# DAC_0.net
KiCad netlist of a schematic drawn in Altium Designer
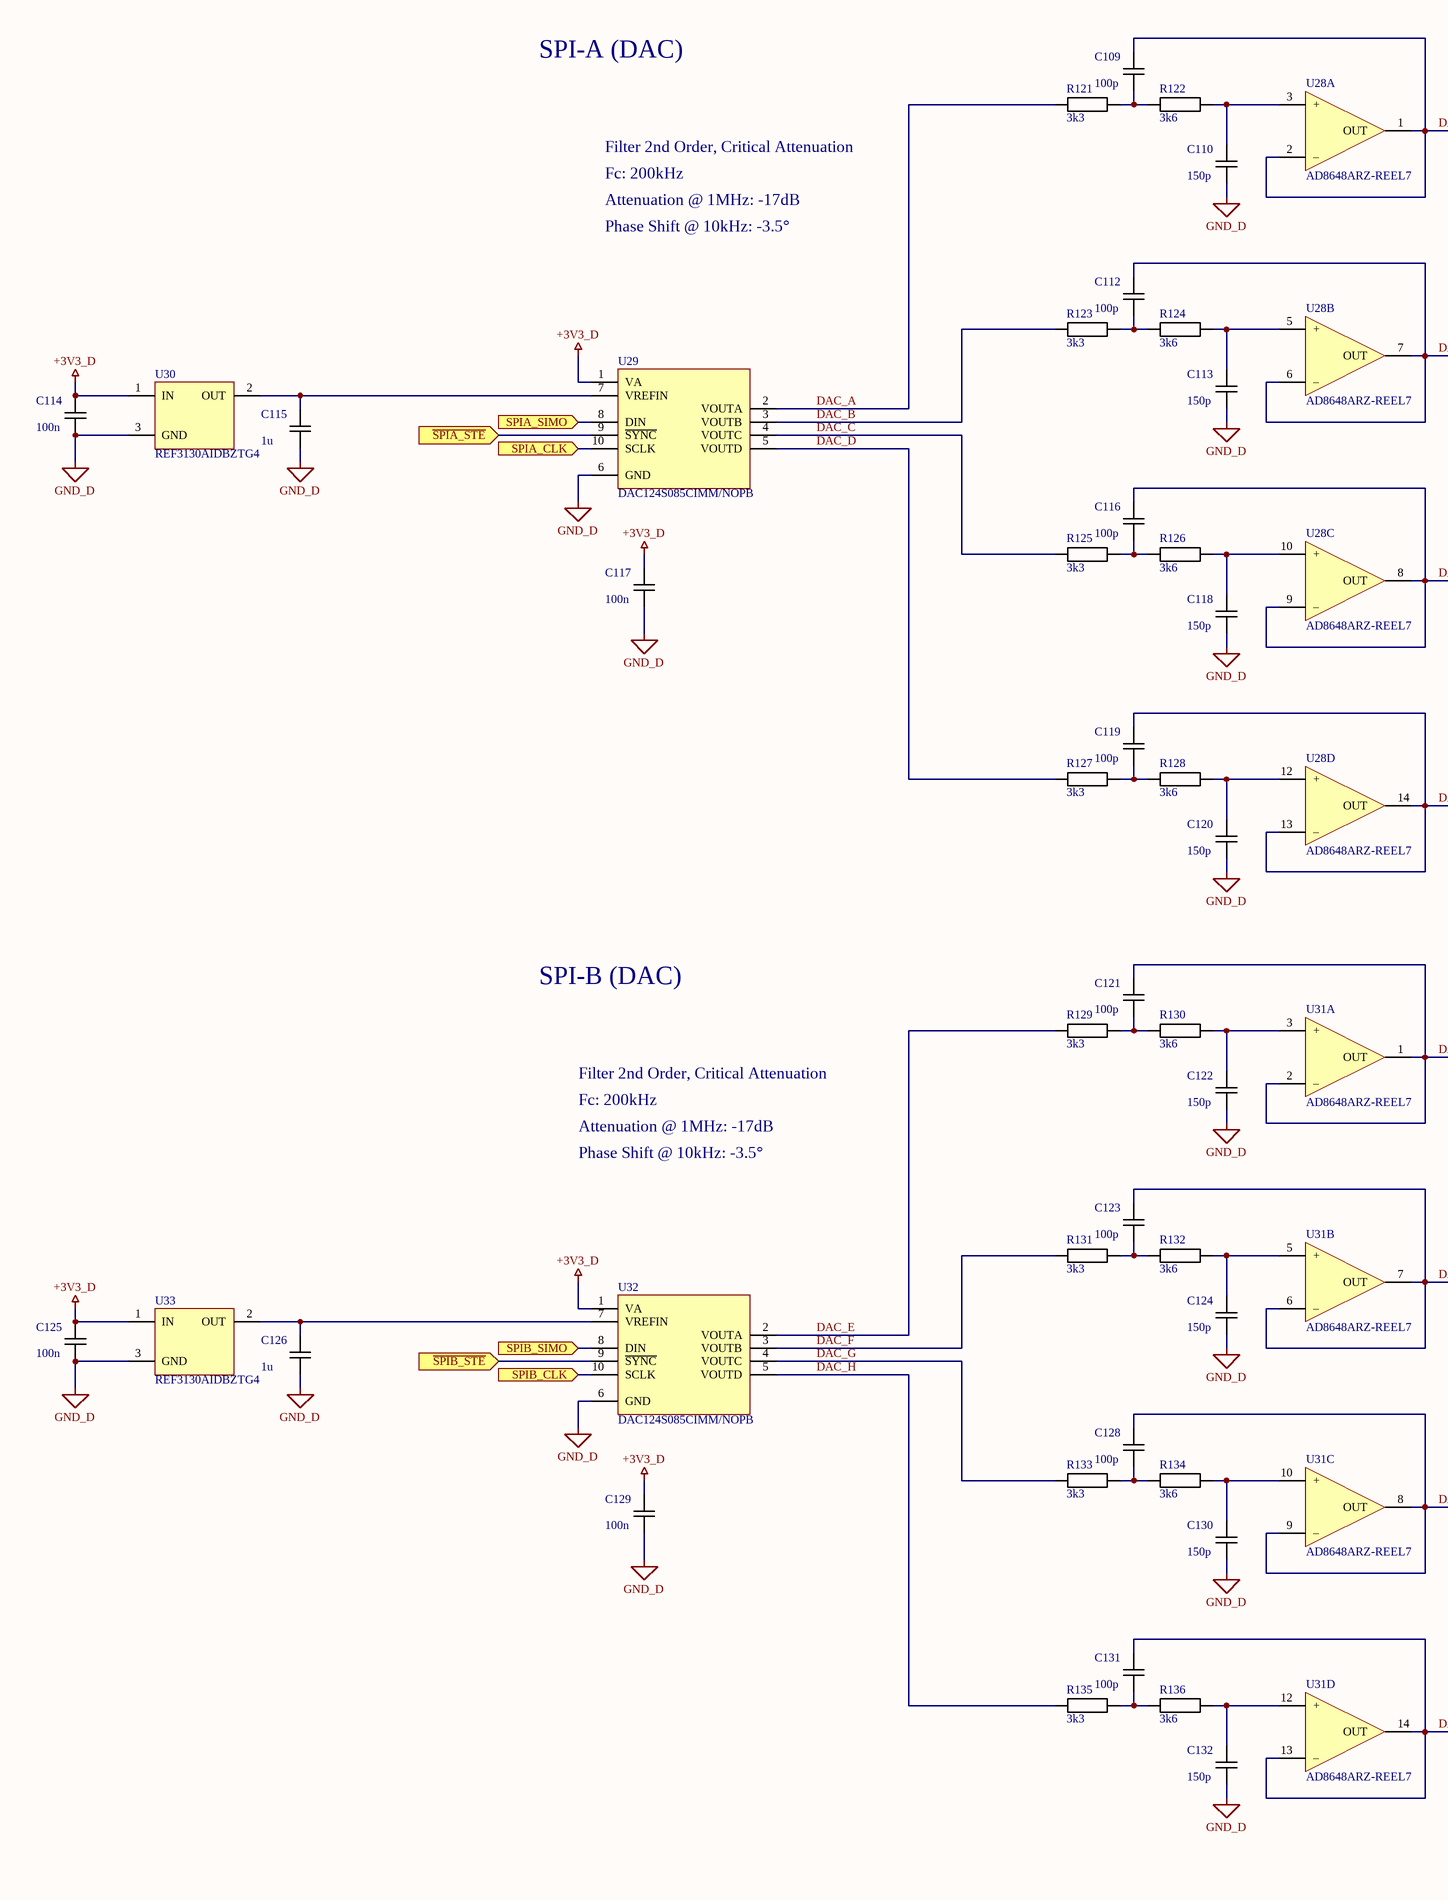
[diagram p0: DAC_0.SchDoc, left]
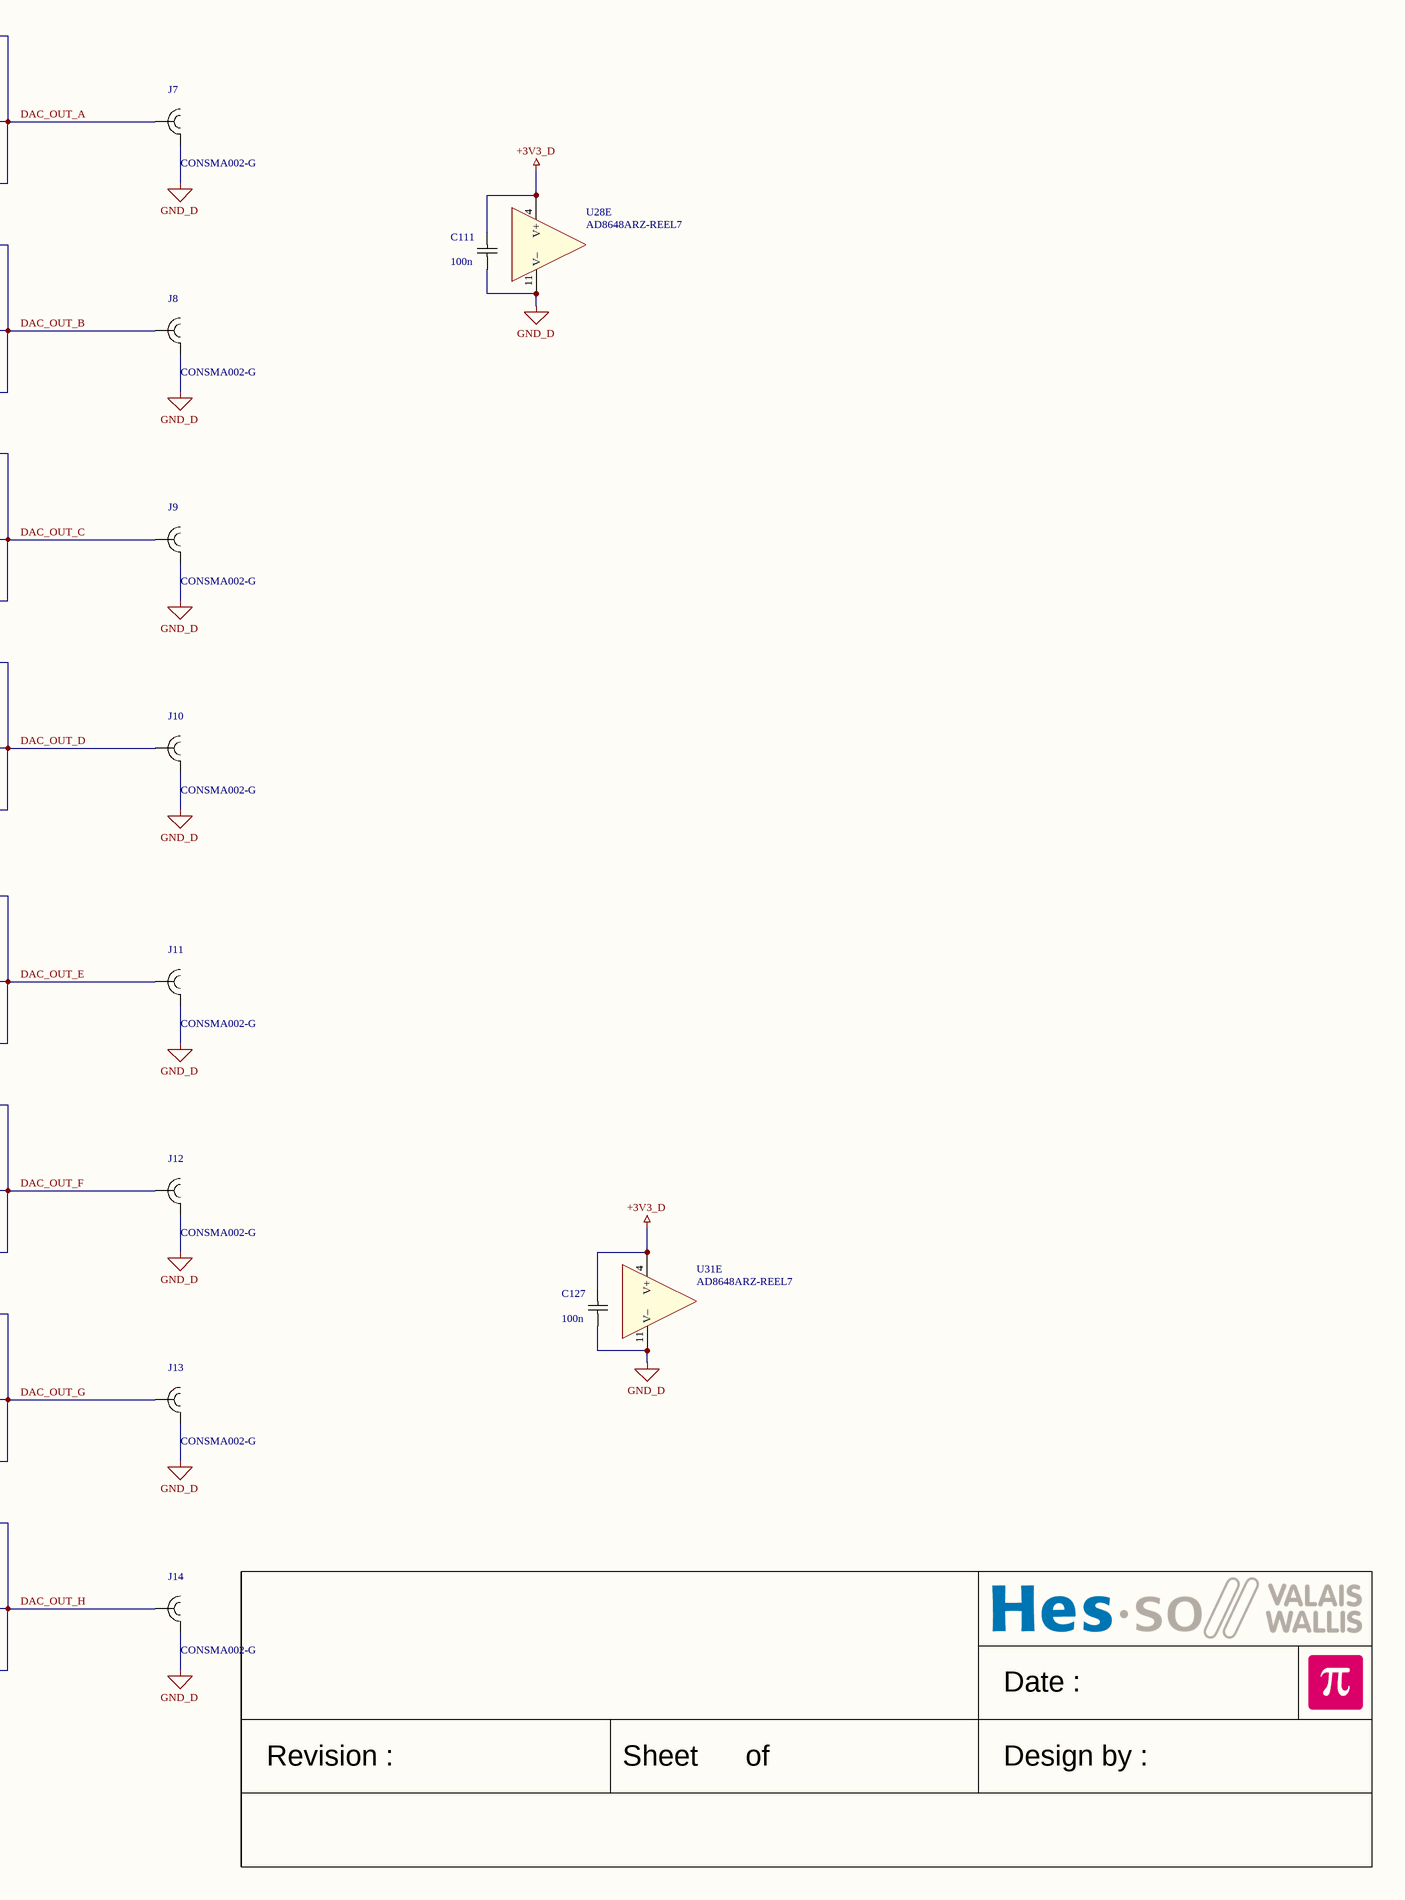
[diagram p1: DAC_0.SchDoc, right]

(export (version "E")
  (design (tool "Eeschema 10.0.6"))
  (components
    (comp (ref "C109")
      (value "100p")
      (footprint "CAPACITOR 2012 REFLOW")
      (description "Capacitor X7R 10% 50V 2012(0805)")
      (libsource (lib "Capacitor") (part "Capacitor"))
    )
    (comp (ref "C110")
      (value "150p")
      (footprint "CAPACITOR 2012 REFLOW")
      (description "Capacitor X7R 10% 50V 2012(0805)")
      (libsource (lib "Capacitor") (part "Capacitor"))
    )
    (comp (ref "C111")
      (value "100n")
      (footprint "CAPACITOR 1608 REFLOW")
      (description "Capacitor X7R 10% 50V 1608(0603)")
      (libsource (lib "Capacitor") (part "Capacitor"))
    )
    (comp (ref "C112")
      (value "100p")
      (footprint "CAPACITOR 2012 REFLOW")
      (description "Capacitor X7R 10% 50V 2012(0805)")
      (libsource (lib "Capacitor") (part "Capacitor"))
    )
    (comp (ref "C113")
      (value "150p")
      (footprint "CAPACITOR 2012 REFLOW")
      (description "Capacitor X7R 10% 50V 2012(0805)")
      (libsource (lib "Capacitor") (part "Capacitor"))
    )
    (comp (ref "C114")
      (value "100n")
      (footprint "CAPACITOR 2012 REFLOW")
      (description "Capacitor X7R 10% 50V 2012(0805)")
      (libsource (lib "Capacitor") (part "Capacitor"))
    )
    (comp (ref "C115")
      (value "1u")
      (footprint "CAPACITOR 2012 REFLOW")
      (description "Capacitor X7R 10% 10V 2012(0805)")
      (libsource (lib "Capacitor") (part "Capacitor"))
    )
    (comp (ref "C116")
      (value "100p")
      (footprint "CAPACITOR 2012 REFLOW")
      (description "Capacitor X7R 10% 50V 2012(0805)")
      (libsource (lib "Capacitor") (part "Capacitor"))
    )
    (comp (ref "C117")
      (value "100n")
      (footprint "CAPACITOR 1608 REFLOW")
      (description "Capacitor X7R 10% 50V 1608(0603)")
      (libsource (lib "Capacitor") (part "Capacitor"))
    )
    (comp (ref "C118")
      (value "150p")
      (footprint "CAPACITOR 2012 REFLOW")
      (description "Capacitor X7R 10% 50V 2012(0805)")
      (libsource (lib "Capacitor") (part "Capacitor"))
    )
    (comp (ref "C119")
      (value "100p")
      (footprint "CAPACITOR 2012 REFLOW")
      (description "Capacitor X7R 10% 50V 2012(0805)")
      (libsource (lib "Capacitor") (part "Capacitor"))
    )
    (comp (ref "C120")
      (value "150p")
      (footprint "CAPACITOR 2012 REFLOW")
      (description "Capacitor X7R 10% 50V 2012(0805)")
      (libsource (lib "Capacitor") (part "Capacitor"))
    )
    (comp (ref "C121")
      (value "100p")
      (footprint "CAPACITOR 2012 REFLOW")
      (description "Capacitor X7R 10% 50V 2012(0805)")
      (libsource (lib "Capacitor") (part "Capacitor"))
    )
    (comp (ref "C122")
      (value "150p")
      (footprint "CAPACITOR 2012 REFLOW")
      (description "Capacitor X7R 10% 50V 2012(0805)")
      (libsource (lib "Capacitor") (part "Capacitor"))
    )
    (comp (ref "C123")
      (value "100p")
      (footprint "CAPACITOR 2012 REFLOW")
      (description "Capacitor X7R 10% 50V 2012(0805)")
      (libsource (lib "Capacitor") (part "Capacitor"))
    )
    (comp (ref "C124")
      (value "150p")
      (footprint "CAPACITOR 2012 REFLOW")
      (description "Capacitor X7R 10% 50V 2012(0805)")
      (libsource (lib "Capacitor") (part "Capacitor"))
    )
    (comp (ref "C125")
      (value "100n")
      (footprint "CAPACITOR 2012 REFLOW")
      (description "Capacitor X7R 10% 50V 2012(0805)")
      (libsource (lib "Capacitor") (part "Capacitor"))
    )
    (comp (ref "C126")
      (value "1u")
      (footprint "CAPACITOR 2012 REFLOW")
      (description "Capacitor X7R 10% 10V 2012(0805)")
      (libsource (lib "Capacitor") (part "Capacitor"))
    )
    (comp (ref "C127")
      (value "100n")
      (footprint "CAPACITOR 1608 REFLOW")
      (description "Capacitor X7R 10% 50V 1608(0603)")
      (libsource (lib "Capacitor") (part "Capacitor"))
    )
    (comp (ref "C128")
      (value "100p")
      (footprint "CAPACITOR 2012 REFLOW")
      (description "Capacitor X7R 10% 50V 2012(0805)")
      (libsource (lib "Capacitor") (part "Capacitor"))
    )
    (comp (ref "C129")
      (value "100n")
      (footprint "CAPACITOR 1608 REFLOW")
      (description "Capacitor X7R 10% 50V 1608(0603)")
      (libsource (lib "Capacitor") (part "Capacitor"))
    )
    (comp (ref "C130")
      (value "150p")
      (footprint "CAPACITOR 2012 REFLOW")
      (description "Capacitor X7R 10% 50V 2012(0805)")
      (libsource (lib "Capacitor") (part "Capacitor"))
    )
    (comp (ref "C131")
      (value "100p")
      (footprint "CAPACITOR 2012 REFLOW")
      (description "Capacitor X7R 10% 50V 2012(0805)")
      (libsource (lib "Capacitor") (part "Capacitor"))
    )
    (comp (ref "C132")
      (value "150p")
      (footprint "CAPACITOR 2012 REFLOW")
      (description "Capacitor X7R 10% 50V 2012(0805)")
      (libsource (lib "Capacitor") (part "Capacitor"))
    )
    (comp (ref "J7")
      (value "CONSMA002-G")
      (footprint "SMA TH Right Angle Linx CONSMA002")
      (description "SMA TH RIGHT ANGLE LINX CONSMA002")
      (fields (field (name "MANUFACTURER") "Linx Technologies"))
      (libsource (lib "Connector") (part "SMA TH RIGHT ANGLE LINX CONSMA002"))
    )
    (comp (ref "J8")
      (value "CONSMA002-G")
      (footprint "SMA TH Right Angle Linx CONSMA002")
      (description "SMA TH RIGHT ANGLE LINX CONSMA002")
      (fields (field (name "MANUFACTURER") "Linx Technologies"))
      (libsource (lib "Connector") (part "SMA TH RIGHT ANGLE LINX CONSMA002"))
    )
    (comp (ref "J9")
      (value "CONSMA002-G")
      (footprint "SMA TH Right Angle Linx CONSMA002")
      (description "SMA TH RIGHT ANGLE LINX CONSMA002")
      (fields (field (name "MANUFACTURER") "Linx Technologies"))
      (libsource (lib "Connector") (part "SMA TH RIGHT ANGLE LINX CONSMA002"))
    )
    (comp (ref "J10")
      (value "CONSMA002-G")
      (footprint "SMA TH Right Angle Linx CONSMA002")
      (description "SMA TH RIGHT ANGLE LINX CONSMA002")
      (fields (field (name "MANUFACTURER") "Linx Technologies"))
      (libsource (lib "Connector") (part "SMA TH RIGHT ANGLE LINX CONSMA002"))
    )
    (comp (ref "J11")
      (value "CONSMA002-G")
      (footprint "SMA TH Right Angle Linx CONSMA002")
      (description "SMA TH RIGHT ANGLE LINX CONSMA002")
      (fields (field (name "MANUFACTURER") "Linx Technologies"))
      (libsource (lib "Connector") (part "SMA TH RIGHT ANGLE LINX CONSMA002"))
    )
    (comp (ref "J12")
      (value "CONSMA002-G")
      (footprint "SMA TH Right Angle Linx CONSMA002")
      (description "SMA TH RIGHT ANGLE LINX CONSMA002")
      (fields (field (name "MANUFACTURER") "Linx Technologies"))
      (libsource (lib "Connector") (part "SMA TH RIGHT ANGLE LINX CONSMA002"))
    )
    (comp (ref "J13")
      (value "CONSMA002-G")
      (footprint "SMA TH Right Angle Linx CONSMA002")
      (description "SMA TH RIGHT ANGLE LINX CONSMA002")
      (fields (field (name "MANUFACTURER") "Linx Technologies"))
      (libsource (lib "Connector") (part "SMA TH RIGHT ANGLE LINX CONSMA002"))
    )
    (comp (ref "J14")
      (value "CONSMA002-G")
      (footprint "SMA TH Right Angle Linx CONSMA002")
      (description "SMA TH RIGHT ANGLE LINX CONSMA002")
      (fields (field (name "MANUFACTURER") "Linx Technologies"))
      (libsource (lib "Connector") (part "SMA TH RIGHT ANGLE LINX CONSMA002"))
    )
    (comp (ref "R121")
      (value "3k3")
      (footprint "RESISTOR 2012 REFLOW")
      (description "Resistor 1% 50V 125mW 2012(0805)")
      (libsource (lib "Resistor") (part "Resistor"))
    )
    (comp (ref "R122")
      (value "3k6")
      (footprint "RESISTOR 2012 REFLOW")
      (description "Resistor 1% 50V 125mW 2012(0805)")
      (libsource (lib "Resistor") (part "Resistor"))
    )
    (comp (ref "R123")
      (value "3k3")
      (footprint "RESISTOR 2012 REFLOW")
      (description "Resistor 1% 50V 125mW 2012(0805)")
      (libsource (lib "Resistor") (part "Resistor"))
    )
    (comp (ref "R124")
      (value "3k6")
      (footprint "RESISTOR 2012 REFLOW")
      (description "Resistor 1% 50V 125mW 2012(0805)")
      (libsource (lib "Resistor") (part "Resistor"))
    )
    (comp (ref "R125")
      (value "3k3")
      (footprint "RESISTOR 2012 REFLOW")
      (description "Resistor 1% 50V 125mW 2012(0805)")
      (libsource (lib "Resistor") (part "Resistor"))
    )
    (comp (ref "R126")
      (value "3k6")
      (footprint "RESISTOR 2012 REFLOW")
      (description "Resistor 1% 50V 125mW 2012(0805)")
      (libsource (lib "Resistor") (part "Resistor"))
    )
    (comp (ref "R127")
      (value "3k3")
      (footprint "RESISTOR 2012 REFLOW")
      (description "Resistor 1% 50V 125mW 2012(0805)")
      (libsource (lib "Resistor") (part "Resistor"))
    )
    (comp (ref "R128")
      (value "3k6")
      (footprint "RESISTOR 2012 REFLOW")
      (description "Resistor 1% 50V 125mW 2012(0805)")
      (libsource (lib "Resistor") (part "Resistor"))
    )
    (comp (ref "R129")
      (value "3k3")
      (footprint "RESISTOR 2012 REFLOW")
      (description "Resistor 1% 50V 125mW 2012(0805)")
      (libsource (lib "Resistor") (part "Resistor"))
    )
    (comp (ref "R130")
      (value "3k6")
      (footprint "RESISTOR 2012 REFLOW")
      (description "Resistor 1% 50V 125mW 2012(0805)")
      (libsource (lib "Resistor") (part "Resistor"))
    )
    (comp (ref "R131")
      (value "3k3")
      (footprint "RESISTOR 2012 REFLOW")
      (description "Resistor 1% 50V 125mW 2012(0805)")
      (libsource (lib "Resistor") (part "Resistor"))
    )
    (comp (ref "R132")
      (value "3k6")
      (footprint "RESISTOR 2012 REFLOW")
      (description "Resistor 1% 50V 125mW 2012(0805)")
      (libsource (lib "Resistor") (part "Resistor"))
    )
    (comp (ref "R133")
      (value "3k3")
      (footprint "RESISTOR 2012 REFLOW")
      (description "Resistor 1% 50V 125mW 2012(0805)")
      (libsource (lib "Resistor") (part "Resistor"))
    )
    (comp (ref "R134")
      (value "3k6")
      (footprint "RESISTOR 2012 REFLOW")
      (description "Resistor 1% 50V 125mW 2012(0805)")
      (libsource (lib "Resistor") (part "Resistor"))
    )
    (comp (ref "R135")
      (value "3k3")
      (footprint "RESISTOR 2012 REFLOW")
      (description "Resistor 1% 50V 125mW 2012(0805)")
      (libsource (lib "Resistor") (part "Resistor"))
    )
    (comp (ref "R136")
      (value "3k6")
      (footprint "RESISTOR 2012 REFLOW")
      (description "Resistor 1% 50V 125mW 2012(0805)")
      (libsource (lib "Resistor") (part "Resistor"))
    )
    (comp (ref "U28")
      (value "AD8648ARZ-REEL7")
      (footprint "SO14 P1.27 C4.0X8.8 H1.75")
      (description "Generic quad OPA 14 pins")
      (fields (field (name "MANUFACTURER") "Analog Devices"))
      (libsource (lib "Amplifier") (part "OPA QUAD"))
    )
    (comp (ref "U29")
      (value "DAC124S085CIMM/NOPB")
      (footprint "VSSOP10 P0.5 C3.1X3.1 H1.1")
      (description "DAC124S085 12-Bit Micro Power Quad Digital-to-Analog Converter With Rail-to-Rail Output")
      (fields (field (name "MANUFACTURER") "Texas Instruments"))
      (libsource (lib "Converter") (part "DAC124S085CIMM"))
    )
    (comp (ref "U30")
      (value "REF3130AIDBZTG4")
      (footprint "SOT23 P0.95 C1.6x3.0 H1.3")
      (description "Generic Positive Voltage Reference")
      (libsource (lib "Regulator") (part "REFERENCE SOT23 IN,OUT,GND"))
    )
    (comp (ref "U31")
      (value "AD8648ARZ-REEL7")
      (footprint "SO14 P1.27 C4.0X8.8 H1.75")
      (description "Generic quad OPA 14 pins")
      (fields (field (name "MANUFACTURER") "Analog Devices"))
      (libsource (lib "Amplifier") (part "OPA QUAD"))
    )
    (comp (ref "U32")
      (value "DAC124S085CIMM/NOPB")
      (footprint "VSSOP10 P0.5 C3.1X3.1 H1.1")
      (description "DAC124S085 12-Bit Micro Power Quad Digital-to-Analog Converter With Rail-to-Rail Output")
      (fields (field (name "MANUFACTURER") "Texas Instruments"))
      (libsource (lib "Converter") (part "DAC124S085CIMM"))
    )
    (comp (ref "U33")
      (value "REF3130AIDBZTG4")
      (footprint "SOT23 P0.95 C1.6x3.0 H1.3")
      (description "Generic Positive Voltage Reference")
      (libsource (lib "Regulator") (part "REFERENCE SOT23 IN,OUT,GND"))
    )
  )
  (nets
    (net (code "1") (name "+3V3_D") (class "Default")
      (node (ref "C111") (pin "2") (pinfunction "2_2") (pintype "passive"))
      (node (ref "C114") (pin "2") (pinfunction "2_2") (pintype "passive"))
      (node (ref "C117") (pin "2") (pinfunction "2_2") (pintype "passive"))
      (node (ref "C125") (pin "2") (pinfunction "2_2") (pintype "passive"))
      (node (ref "C127") (pin "2") (pinfunction "2_2") (pintype "passive"))
      (node (ref "C129") (pin "2") (pinfunction "2_2") (pintype "passive"))
      (node (ref "U28") (pin "4") (pinfunction "V+_4") (pintype "passive"))
      (node (ref "U29") (pin "1") (pinfunction "VA_1") (pintype "passive"))
      (node (ref "U30") (pin "1") (pinfunction "IN_1") (pintype "passive"))
      (node (ref "U31") (pin "4") (pinfunction "V+_4") (pintype "passive"))
      (node (ref "U32") (pin "1") (pinfunction "VA_1") (pintype "passive"))
      (node (ref "U33") (pin "1") (pinfunction "IN_1") (pintype "passive"))
    )
    (net (code "2") (name "/DAC_A") (class "Default")
      (node (ref "R121") (pin "1") (pinfunction "1_1") (pintype "passive"))
      (node (ref "U29") (pin "2") (pinfunction "VOUTA_2") (pintype "passive"))
    )
    (net (code "3") (name "/DAC_B") (class "Default")
      (node (ref "R123") (pin "1") (pinfunction "1_1") (pintype "passive"))
      (node (ref "U29") (pin "3") (pinfunction "VOUTB_3") (pintype "passive"))
    )
    (net (code "4") (name "/DAC_C") (class "Default")
      (node (ref "R125") (pin "1") (pinfunction "1_1") (pintype "passive"))
      (node (ref "U29") (pin "4") (pinfunction "VOUTC_4") (pintype "passive"))
    )
    (net (code "5") (name "/DAC_D") (class "Default")
      (node (ref "R127") (pin "1") (pinfunction "1_1") (pintype "passive"))
      (node (ref "U29") (pin "5") (pinfunction "VOUTD_5") (pintype "passive"))
    )
    (net (code "6") (name "/DAC_E") (class "Default")
      (node (ref "R129") (pin "1") (pinfunction "1_1") (pintype "passive"))
      (node (ref "U32") (pin "2") (pinfunction "VOUTA_2") (pintype "passive"))
    )
    (net (code "7") (name "/DAC_F") (class "Default")
      (node (ref "R131") (pin "1") (pinfunction "1_1") (pintype "passive"))
      (node (ref "U32") (pin "3") (pinfunction "VOUTB_3") (pintype "passive"))
    )
    (net (code "8") (name "/DAC_G") (class "Default")
      (node (ref "R133") (pin "1") (pinfunction "1_1") (pintype "passive"))
      (node (ref "U32") (pin "4") (pinfunction "VOUTC_4") (pintype "passive"))
    )
    (net (code "9") (name "/DAC_H") (class "Default")
      (node (ref "R135") (pin "1") (pinfunction "1_1") (pintype "passive"))
      (node (ref "U32") (pin "5") (pinfunction "VOUTD_5") (pintype "passive"))
    )
    (net (code "10") (name "/DAC_OUT_A") (class "Default")
      (node (ref "C109") (pin "2") (pinfunction "2_2") (pintype "passive"))
      (node (ref "J7") (pin "1") (pinfunction "1_1") (pintype "passive"))
      (node (ref "U28") (pin "1") (pinfunction "OUT_1") (pintype "passive"))
      (node (ref "U28") (pin "2") (pinfunction "–_2") (pintype "passive"))
    )
    (net (code "11") (name "/DAC_OUT_B") (class "Default")
      (node (ref "C112") (pin "2") (pinfunction "2_2") (pintype "passive"))
      (node (ref "J8") (pin "1") (pinfunction "1_1") (pintype "passive"))
      (node (ref "U28") (pin "6") (pinfunction "–_6") (pintype "passive"))
      (node (ref "U28") (pin "7") (pinfunction "OUT_7") (pintype "passive"))
    )
    (net (code "12") (name "/DAC_OUT_C") (class "Default")
      (node (ref "C116") (pin "2") (pinfunction "2_2") (pintype "passive"))
      (node (ref "J9") (pin "1") (pinfunction "1_1") (pintype "passive"))
      (node (ref "U28") (pin "8") (pinfunction "OUT_8") (pintype "passive"))
      (node (ref "U28") (pin "9") (pinfunction "–_9") (pintype "passive"))
    )
    (net (code "13") (name "/DAC_OUT_D") (class "Default")
      (node (ref "C119") (pin "2") (pinfunction "2_2") (pintype "passive"))
      (node (ref "J10") (pin "1") (pinfunction "1_1") (pintype "passive"))
      (node (ref "U28") (pin "13") (pinfunction "–_13") (pintype "passive"))
      (node (ref "U28") (pin "14") (pinfunction "OUT_14") (pintype "passive"))
    )
    (net (code "14") (name "/DAC_OUT_E") (class "Default")
      (node (ref "C121") (pin "2") (pinfunction "2_2") (pintype "passive"))
      (node (ref "J11") (pin "1") (pinfunction "1_1") (pintype "passive"))
      (node (ref "U31") (pin "1") (pinfunction "OUT_1") (pintype "passive"))
      (node (ref "U31") (pin "2") (pinfunction "–_2") (pintype "passive"))
    )
    (net (code "15") (name "/DAC_OUT_F") (class "Default")
      (node (ref "C123") (pin "2") (pinfunction "2_2") (pintype "passive"))
      (node (ref "J12") (pin "1") (pinfunction "1_1") (pintype "passive"))
      (node (ref "U31") (pin "6") (pinfunction "–_6") (pintype "passive"))
      (node (ref "U31") (pin "7") (pinfunction "OUT_7") (pintype "passive"))
    )
    (net (code "16") (name "/DAC_OUT_G") (class "Default")
      (node (ref "C128") (pin "2") (pinfunction "2_2") (pintype "passive"))
      (node (ref "J13") (pin "1") (pinfunction "1_1") (pintype "passive"))
      (node (ref "U31") (pin "8") (pinfunction "OUT_8") (pintype "passive"))
      (node (ref "U31") (pin "9") (pinfunction "–_9") (pintype "passive"))
    )
    (net (code "17") (name "/DAC_OUT_H") (class "Default")
      (node (ref "C131") (pin "2") (pinfunction "2_2") (pintype "passive"))
      (node (ref "J14") (pin "1") (pinfunction "1_1") (pintype "passive"))
      (node (ref "U31") (pin "13") (pinfunction "–_13") (pintype "passive"))
      (node (ref "U31") (pin "14") (pinfunction "OUT_14") (pintype "passive"))
    )
    (net (code "18") (name "/SPIA_CLK") (class "Default")
      (node (ref "U29") (pin "10") (pinfunction "SCLK_10") (pintype "passive"))
    )
    (net (code "19") (name "/SPIA_SIMO") (class "Default")
      (node (ref "U29") (pin "8") (pinfunction "DIN_8") (pintype "passive"))
    )
    (net (code "20") (name "/SPIB_CLK") (class "Default")
      (node (ref "U32") (pin "10") (pinfunction "SCLK_10") (pintype "passive"))
    )
    (net (code "21") (name "/SPIB_SIMO") (class "Default")
      (node (ref "U32") (pin "8") (pinfunction "DIN_8") (pintype "passive"))
    )
    (net (code "22") (name "/~{SPIA_STE}") (class "Default")
      (node (ref "U29") (pin "9") (pinfunction "~{SYNC}_9") (pintype "passive"))
    )
    (net (code "23") (name "/~{SPIB_STE}") (class "Default")
      (node (ref "U32") (pin "9") (pinfunction "~{SYNC}_9") (pintype "passive"))
    )
    (net (code "24") (name "GND_D") (class "Default")
      (node (ref "C110") (pin "1") (pinfunction "1_1") (pintype "passive"))
      (node (ref "C111") (pin "1") (pinfunction "1_1") (pintype "passive"))
      (node (ref "C113") (pin "1") (pinfunction "1_1") (pintype "passive"))
      (node (ref "C114") (pin "1") (pinfunction "1_1") (pintype "passive"))
      (node (ref "C115") (pin "1") (pinfunction "1_1") (pintype "passive"))
      (node (ref "C117") (pin "1") (pinfunction "1_1") (pintype "passive"))
      (node (ref "C118") (pin "1") (pinfunction "1_1") (pintype "passive"))
      (node (ref "C120") (pin "1") (pinfunction "1_1") (pintype "passive"))
      (node (ref "C122") (pin "1") (pinfunction "1_1") (pintype "passive"))
      (node (ref "C124") (pin "1") (pinfunction "1_1") (pintype "passive"))
      (node (ref "C125") (pin "1") (pinfunction "1_1") (pintype "passive"))
      (node (ref "C126") (pin "1") (pinfunction "1_1") (pintype "passive"))
      (node (ref "C127") (pin "1") (pinfunction "1_1") (pintype "passive"))
      (node (ref "C129") (pin "1") (pinfunction "1_1") (pintype "passive"))
      (node (ref "C130") (pin "1") (pinfunction "1_1") (pintype "passive"))
      (node (ref "C132") (pin "1") (pinfunction "1_1") (pintype "passive"))
      (node (ref "J10") (pin "2") (pinfunction "2_2") (pintype "passive"))
      (node (ref "J11") (pin "2") (pinfunction "2_2") (pintype "passive"))
      (node (ref "J12") (pin "2") (pinfunction "2_2") (pintype "passive"))
      (node (ref "J13") (pin "2") (pinfunction "2_2") (pintype "passive"))
      (node (ref "J14") (pin "2") (pinfunction "2_2") (pintype "passive"))
      (node (ref "J7") (pin "2") (pinfunction "2_2") (pintype "passive"))
      (node (ref "J8") (pin "2") (pinfunction "2_2") (pintype "passive"))
      (node (ref "J9") (pin "2") (pinfunction "2_2") (pintype "passive"))
      (node (ref "U28") (pin "11") (pinfunction "V–_11") (pintype "passive"))
      (node (ref "U29") (pin "6") (pinfunction "GND_6") (pintype "passive"))
      (node (ref "U30") (pin "3") (pinfunction "GND_3") (pintype "passive"))
      (node (ref "U31") (pin "11") (pinfunction "V–_11") (pintype "passive"))
      (node (ref "U32") (pin "6") (pinfunction "GND_6") (pintype "passive"))
      (node (ref "U33") (pin "3") (pinfunction "GND_3") (pintype "passive"))
    )
    (net (code "25") (name "Net-(C109-Pad1)") (class "Default")
      (node (ref "C109") (pin "1") (pinfunction "1_1") (pintype "passive"))
      (node (ref "R121") (pin "2") (pinfunction "2_2") (pintype "passive"))
      (node (ref "R122") (pin "1") (pinfunction "1_1") (pintype "passive"))
    )
    (net (code "26") (name "Net-(C112-Pad1)") (class "Default")
      (node (ref "C112") (pin "1") (pinfunction "1_1") (pintype "passive"))
      (node (ref "R123") (pin "2") (pinfunction "2_2") (pintype "passive"))
      (node (ref "R124") (pin "1") (pinfunction "1_1") (pintype "passive"))
    )
    (net (code "27") (name "Net-(C116-Pad1)") (class "Default")
      (node (ref "C116") (pin "1") (pinfunction "1_1") (pintype "passive"))
      (node (ref "R125") (pin "2") (pinfunction "2_2") (pintype "passive"))
      (node (ref "R126") (pin "1") (pinfunction "1_1") (pintype "passive"))
    )
    (net (code "28") (name "Net-(C119-Pad1)") (class "Default")
      (node (ref "C119") (pin "1") (pinfunction "1_1") (pintype "passive"))
      (node (ref "R127") (pin "2") (pinfunction "2_2") (pintype "passive"))
      (node (ref "R128") (pin "1") (pinfunction "1_1") (pintype "passive"))
    )
    (net (code "29") (name "Net-(C121-Pad1)") (class "Default")
      (node (ref "C121") (pin "1") (pinfunction "1_1") (pintype "passive"))
      (node (ref "R129") (pin "2") (pinfunction "2_2") (pintype "passive"))
      (node (ref "R130") (pin "1") (pinfunction "1_1") (pintype "passive"))
    )
    (net (code "30") (name "Net-(C123-Pad1)") (class "Default")
      (node (ref "C123") (pin "1") (pinfunction "1_1") (pintype "passive"))
      (node (ref "R131") (pin "2") (pinfunction "2_2") (pintype "passive"))
      (node (ref "R132") (pin "1") (pinfunction "1_1") (pintype "passive"))
    )
    (net (code "31") (name "Net-(C128-Pad1)") (class "Default")
      (node (ref "C128") (pin "1") (pinfunction "1_1") (pintype "passive"))
      (node (ref "R133") (pin "2") (pinfunction "2_2") (pintype "passive"))
      (node (ref "R134") (pin "1") (pinfunction "1_1") (pintype "passive"))
    )
    (net (code "32") (name "Net-(C131-Pad1)") (class "Default")
      (node (ref "C131") (pin "1") (pinfunction "1_1") (pintype "passive"))
      (node (ref "R135") (pin "2") (pinfunction "2_2") (pintype "passive"))
      (node (ref "R136") (pin "1") (pinfunction "1_1") (pintype "passive"))
    )
    (net (code "33") (name "Net-(U28A-+)") (class "Default")
      (node (ref "C110") (pin "2") (pinfunction "2_2") (pintype "passive"))
      (node (ref "R122") (pin "2") (pinfunction "2_2") (pintype "passive"))
      (node (ref "U28") (pin "3") (pinfunction "+_3") (pintype "passive"))
    )
    (net (code "34") (name "Net-(U28B-+)") (class "Default")
      (node (ref "C113") (pin "2") (pinfunction "2_2") (pintype "passive"))
      (node (ref "R124") (pin "2") (pinfunction "2_2") (pintype "passive"))
      (node (ref "U28") (pin "5") (pinfunction "+_5") (pintype "passive"))
    )
    (net (code "35") (name "Net-(U28C-+)") (class "Default")
      (node (ref "C118") (pin "2") (pinfunction "2_2") (pintype "passive"))
      (node (ref "R126") (pin "2") (pinfunction "2_2") (pintype "passive"))
      (node (ref "U28") (pin "10") (pinfunction "+_10") (pintype "passive"))
    )
    (net (code "36") (name "Net-(U28D-+)") (class "Default")
      (node (ref "C120") (pin "2") (pinfunction "2_2") (pintype "passive"))
      (node (ref "R128") (pin "2") (pinfunction "2_2") (pintype "passive"))
      (node (ref "U28") (pin "12") (pinfunction "+_12") (pintype "passive"))
    )
    (net (code "37") (name "Net-(U29-VREFIN)") (class "Default")
      (node (ref "C115") (pin "2") (pinfunction "2_2") (pintype "passive"))
      (node (ref "U29") (pin "7") (pinfunction "VREFIN_7") (pintype "passive"))
      (node (ref "U30") (pin "2") (pinfunction "OUT_2") (pintype "passive"))
    )
    (net (code "38") (name "Net-(U31A-+)") (class "Default")
      (node (ref "C122") (pin "2") (pinfunction "2_2") (pintype "passive"))
      (node (ref "R130") (pin "2") (pinfunction "2_2") (pintype "passive"))
      (node (ref "U31") (pin "3") (pinfunction "+_3") (pintype "passive"))
    )
    (net (code "39") (name "Net-(U31B-+)") (class "Default")
      (node (ref "C124") (pin "2") (pinfunction "2_2") (pintype "passive"))
      (node (ref "R132") (pin "2") (pinfunction "2_2") (pintype "passive"))
      (node (ref "U31") (pin "5") (pinfunction "+_5") (pintype "passive"))
    )
    (net (code "40") (name "Net-(U31C-+)") (class "Default")
      (node (ref "C130") (pin "2") (pinfunction "2_2") (pintype "passive"))
      (node (ref "R134") (pin "2") (pinfunction "2_2") (pintype "passive"))
      (node (ref "U31") (pin "10") (pinfunction "+_10") (pintype "passive"))
    )
    (net (code "41") (name "Net-(U31D-+)") (class "Default")
      (node (ref "C132") (pin "2") (pinfunction "2_2") (pintype "passive"))
      (node (ref "R136") (pin "2") (pinfunction "2_2") (pintype "passive"))
      (node (ref "U31") (pin "12") (pinfunction "+_12") (pintype "passive"))
    )
    (net (code "42") (name "Net-(U32-VREFIN)") (class "Default")
      (node (ref "C126") (pin "2") (pinfunction "2_2") (pintype "passive"))
      (node (ref "U32") (pin "7") (pinfunction "VREFIN_7") (pintype "passive"))
      (node (ref "U33") (pin "2") (pinfunction "OUT_2") (pintype "passive"))
    )
  )
)
